# LEDCube.net
KiCad netlist of a schematic drawn in EAGLE
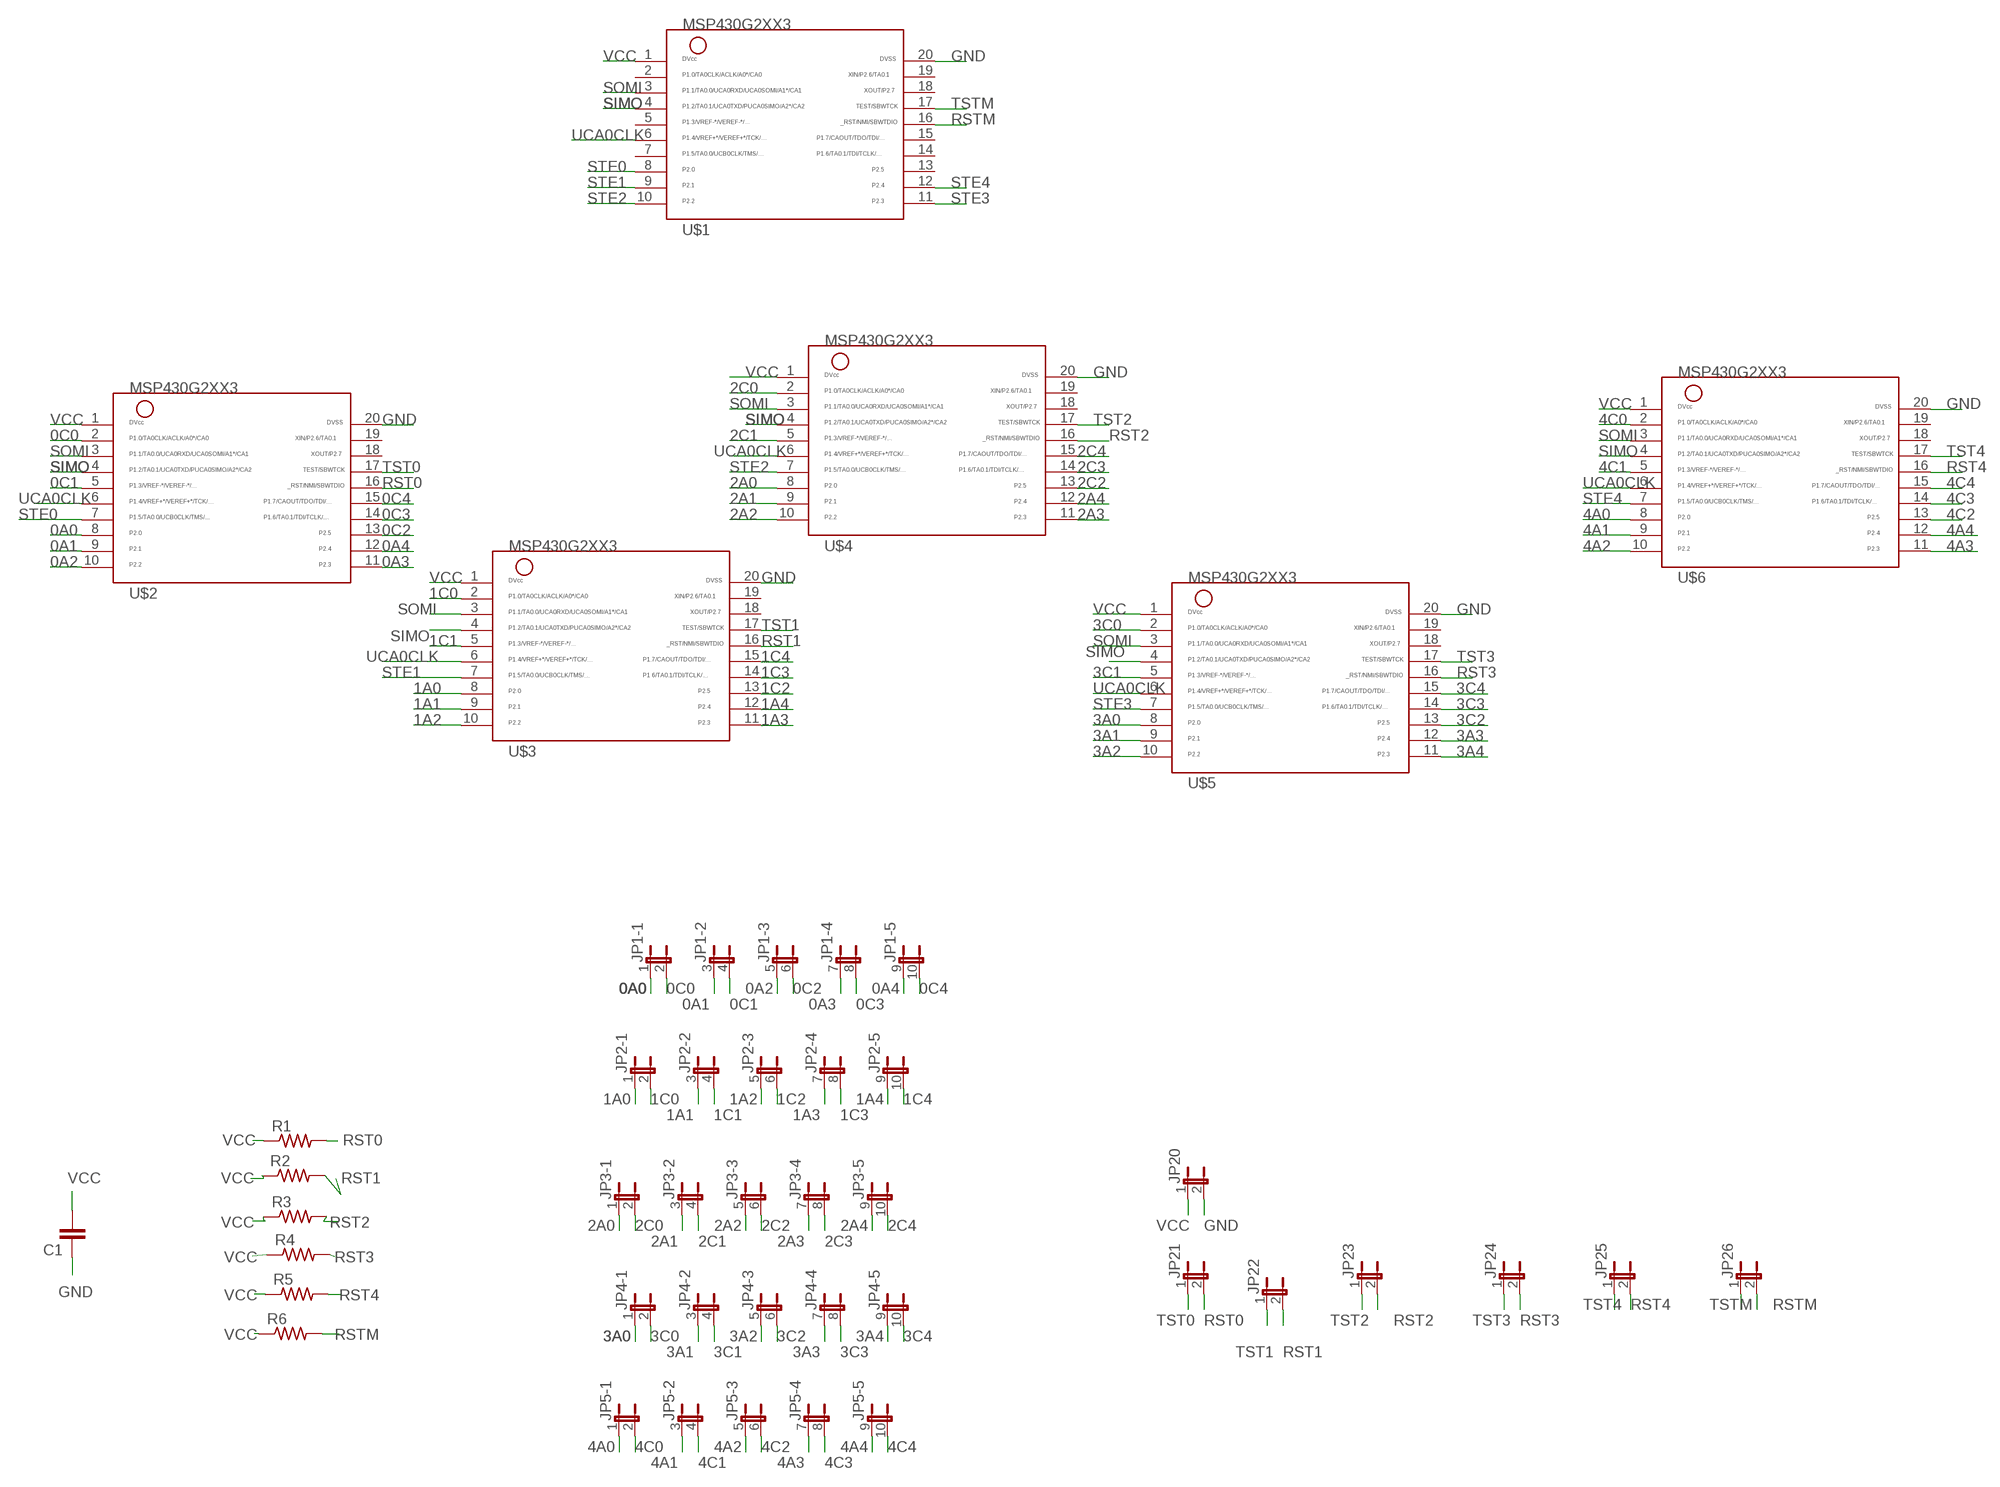
[diagram p0: schematic, sheet 1]

(export (version "E")
  (design (tool "Eeschema 10.0.6"))
  (components
    (comp (ref "C1")
      (value "CC1206")
      (footprint "eagle-import:C1206")
      (libsource (lib "eagle-import") (part "CC1206"))
    )
    (comp (ref "JP1")
      (value "JP5QE")
      (footprint "eagle-import:JP5Q")
      (libsource (lib "eagle-import") (part "JP5QE"))
    )
    (comp (ref "JP2")
      (value "JP5QE")
      (footprint "eagle-import:JP5Q")
      (libsource (lib "eagle-import") (part "JP5QE"))
    )
    (comp (ref "JP3")
      (value "JP5QE")
      (footprint "eagle-import:JP5Q")
      (libsource (lib "eagle-import") (part "JP5QE"))
    )
    (comp (ref "JP4")
      (value "JP5QE")
      (footprint "eagle-import:JP5Q")
      (libsource (lib "eagle-import") (part "JP5QE"))
    )
    (comp (ref "JP5")
      (value "JP5QE")
      (footprint "eagle-import:JP5Q")
      (libsource (lib "eagle-import") (part "JP5QE"))
    )
    (comp (ref "JP20")
      (value "JP1E")
      (footprint "eagle-import:JP1")
      (libsource (lib "eagle-import") (part "JP1E"))
    )
    (comp (ref "JP21")
      (value "JP1E")
      (footprint "eagle-import:JP1")
      (libsource (lib "eagle-import") (part "JP1E"))
    )
    (comp (ref "JP22")
      (value "JP1E")
      (footprint "eagle-import:JP1")
      (libsource (lib "eagle-import") (part "JP1E"))
    )
    (comp (ref "JP23")
      (value "JP1E")
      (footprint "eagle-import:JP1")
      (libsource (lib "eagle-import") (part "JP1E"))
    )
    (comp (ref "JP24")
      (value "JP1E")
      (footprint "eagle-import:JP1")
      (libsource (lib "eagle-import") (part "JP1E"))
    )
    (comp (ref "JP25")
      (value "JP1E")
      (footprint "eagle-import:JP1")
      (libsource (lib "eagle-import") (part "JP1E"))
    )
    (comp (ref "JP26")
      (value "JP1E")
      (footprint "eagle-import:JP1")
      (libsource (lib "eagle-import") (part "JP1E"))
    )
    (comp (ref "R1")
      (value "R-US_R1206")
      (footprint "eagle-import:R1206")
      (libsource (lib "eagle-import") (part "R-US_R1206"))
    )
    (comp (ref "R2")
      (value "R-US_R1206")
      (footprint "eagle-import:R1206")
      (libsource (lib "eagle-import") (part "R-US_R1206"))
    )
    (comp (ref "R3")
      (value "R-US_R1206")
      (footprint "eagle-import:R1206")
      (libsource (lib "eagle-import") (part "R-US_R1206"))
    )
    (comp (ref "R4")
      (value "R-US_R1206")
      (footprint "eagle-import:R1206")
      (libsource (lib "eagle-import") (part "R-US_R1206"))
    )
    (comp (ref "R5")
      (value "R-US_R1206")
      (footprint "eagle-import:R1206")
      (libsource (lib "eagle-import") (part "R-US_R1206"))
    )
    (comp (ref "R6")
      (value "R-US_R1206")
      (footprint "eagle-import:R1206")
      (libsource (lib "eagle-import") (part "R-US_R1206"))
    )
    (comp (ref "U$1")
      (value "MSP430G2XX3TSSOP")
      (footprint "eagle-import:PW20")
      (libsource (lib "eagle-import") (part "MSP430G2XX3TSSOP"))
    )
    (comp (ref "U$2")
      (value "MSP430G2XX3TSSOP")
      (footprint "eagle-import:PW20")
      (libsource (lib "eagle-import") (part "MSP430G2XX3TSSOP"))
    )
    (comp (ref "U$3")
      (value "MSP430G2XX3TSSOP")
      (footprint "eagle-import:PW20")
      (libsource (lib "eagle-import") (part "MSP430G2XX3TSSOP"))
    )
    (comp (ref "U$4")
      (value "MSP430G2XX3TSSOP")
      (footprint "eagle-import:PW20")
      (libsource (lib "eagle-import") (part "MSP430G2XX3TSSOP"))
    )
    (comp (ref "U$5")
      (value "MSP430G2XX3TSSOP")
      (footprint "eagle-import:PW20")
      (libsource (lib "eagle-import") (part "MSP430G2XX3TSSOP"))
    )
    (comp (ref "U$6")
      (value "MSP430G2XX3TSSOP")
      (footprint "eagle-import:PW20")
      (libsource (lib "eagle-import") (part "MSP430G2XX3TSSOP"))
    )
  )
  (nets
    (net (code "1") (name "/0A0") (class "Default")
      (node (ref "JP1") (pin "1") (pinfunction "1_1") (pintype "passive"))
      (node (ref "U$2") (pin "8") (pinfunction "8_8") (pintype "bidirectional"))
    )
    (net (code "2") (name "/0A1") (class "Default")
      (node (ref "JP1") (pin "3") (pinfunction "1_3") (pintype "passive"))
      (node (ref "U$2") (pin "9") (pinfunction "9_9") (pintype "bidirectional"))
    )
    (net (code "3") (name "/0A2") (class "Default")
      (node (ref "JP1") (pin "5") (pinfunction "1_5") (pintype "passive"))
      (node (ref "U$2") (pin "10") (pinfunction "10_10") (pintype "bidirectional"))
    )
    (net (code "4") (name "/0A3") (class "Default")
      (node (ref "JP1") (pin "7") (pinfunction "1_7") (pintype "passive"))
      (node (ref "U$2") (pin "11") (pinfunction "11_11") (pintype "bidirectional"))
    )
    (net (code "5") (name "/0A4") (class "Default")
      (node (ref "JP1") (pin "9") (pinfunction "1_9") (pintype "passive"))
      (node (ref "U$2") (pin "12") (pinfunction "12_12") (pintype "bidirectional"))
    )
    (net (code "6") (name "/0C0") (class "Default")
      (node (ref "JP1") (pin "2") (pinfunction "2_2") (pintype "passive"))
      (node (ref "U$2") (pin "2") (pinfunction "2_2") (pintype "bidirectional"))
    )
    (net (code "7") (name "/0C1") (class "Default")
      (node (ref "JP1") (pin "4") (pinfunction "2_4") (pintype "passive"))
      (node (ref "U$2") (pin "5") (pinfunction "5_5") (pintype "bidirectional"))
    )
    (net (code "8") (name "/0C2") (class "Default")
      (node (ref "JP1") (pin "6") (pinfunction "2_6") (pintype "passive"))
      (node (ref "U$2") (pin "13") (pinfunction "13_13") (pintype "bidirectional"))
    )
    (net (code "9") (name "/0C3") (class "Default")
      (node (ref "JP1") (pin "8") (pinfunction "2_8") (pintype "passive"))
      (node (ref "U$2") (pin "14") (pinfunction "14_14") (pintype "bidirectional"))
    )
    (net (code "10") (name "/0C4") (class "Default")
      (node (ref "JP1") (pin "10") (pinfunction "2_10") (pintype "passive"))
      (node (ref "U$2") (pin "15") (pinfunction "15_15") (pintype "bidirectional"))
    )
    (net (code "11") (name "/1A0") (class "Default")
      (node (ref "JP2") (pin "1") (pinfunction "1_1") (pintype "passive"))
      (node (ref "U$3") (pin "8") (pinfunction "8_8") (pintype "bidirectional"))
    )
    (net (code "12") (name "/1A1") (class "Default")
      (node (ref "JP2") (pin "3") (pinfunction "1_3") (pintype "passive"))
      (node (ref "U$3") (pin "9") (pinfunction "9_9") (pintype "bidirectional"))
    )
    (net (code "13") (name "/1A2") (class "Default")
      (node (ref "JP2") (pin "5") (pinfunction "1_5") (pintype "passive"))
      (node (ref "U$3") (pin "10") (pinfunction "10_10") (pintype "bidirectional"))
    )
    (net (code "14") (name "/1A3") (class "Default")
      (node (ref "JP2") (pin "7") (pinfunction "1_7") (pintype "passive"))
      (node (ref "U$3") (pin "11") (pinfunction "11_11") (pintype "bidirectional"))
    )
    (net (code "15") (name "/1A4") (class "Default")
      (node (ref "JP2") (pin "9") (pinfunction "1_9") (pintype "passive"))
      (node (ref "U$3") (pin "12") (pinfunction "12_12") (pintype "bidirectional"))
    )
    (net (code "16") (name "/1C0") (class "Default")
      (node (ref "JP2") (pin "2") (pinfunction "2_2") (pintype "passive"))
      (node (ref "U$3") (pin "2") (pinfunction "2_2") (pintype "bidirectional"))
    )
    (net (code "17") (name "/1C1") (class "Default")
      (node (ref "JP2") (pin "4") (pinfunction "2_4") (pintype "passive"))
      (node (ref "U$3") (pin "5") (pinfunction "5_5") (pintype "bidirectional"))
    )
    (net (code "18") (name "/1C2") (class "Default")
      (node (ref "JP2") (pin "6") (pinfunction "2_6") (pintype "passive"))
      (node (ref "U$3") (pin "13") (pinfunction "13_13") (pintype "bidirectional"))
    )
    (net (code "19") (name "/1C3") (class "Default")
      (node (ref "JP2") (pin "8") (pinfunction "2_8") (pintype "passive"))
      (node (ref "U$3") (pin "14") (pinfunction "14_14") (pintype "bidirectional"))
    )
    (net (code "20") (name "/1C4") (class "Default")
      (node (ref "JP2") (pin "10") (pinfunction "2_10") (pintype "passive"))
      (node (ref "U$3") (pin "15") (pinfunction "15_15") (pintype "bidirectional"))
    )
    (net (code "21") (name "/2A0") (class "Default")
      (node (ref "JP3") (pin "1") (pinfunction "1_1") (pintype "passive"))
      (node (ref "U$4") (pin "8") (pinfunction "8_8") (pintype "bidirectional"))
    )
    (net (code "22") (name "/2A1") (class "Default")
      (node (ref "JP3") (pin "3") (pinfunction "1_3") (pintype "passive"))
      (node (ref "U$4") (pin "9") (pinfunction "9_9") (pintype "bidirectional"))
    )
    (net (code "23") (name "/2A2") (class "Default")
      (node (ref "JP3") (pin "5") (pinfunction "1_5") (pintype "passive"))
      (node (ref "U$4") (pin "10") (pinfunction "10_10") (pintype "bidirectional"))
    )
    (net (code "24") (name "/2A3") (class "Default")
      (node (ref "JP3") (pin "7") (pinfunction "1_7") (pintype "passive"))
      (node (ref "U$4") (pin "11") (pinfunction "11_11") (pintype "bidirectional"))
    )
    (net (code "25") (name "/2A4") (class "Default")
      (node (ref "JP3") (pin "9") (pinfunction "1_9") (pintype "passive"))
      (node (ref "U$4") (pin "12") (pinfunction "12_12") (pintype "bidirectional"))
    )
    (net (code "26") (name "/2C0") (class "Default")
      (node (ref "JP3") (pin "2") (pinfunction "2_2") (pintype "passive"))
      (node (ref "U$4") (pin "2") (pinfunction "2_2") (pintype "bidirectional"))
    )
    (net (code "27") (name "/2C1") (class "Default")
      (node (ref "JP3") (pin "4") (pinfunction "2_4") (pintype "passive"))
      (node (ref "U$4") (pin "5") (pinfunction "5_5") (pintype "bidirectional"))
    )
    (net (code "28") (name "/2C2") (class "Default")
      (node (ref "JP3") (pin "6") (pinfunction "2_6") (pintype "passive"))
      (node (ref "U$4") (pin "13") (pinfunction "13_13") (pintype "bidirectional"))
    )
    (net (code "29") (name "/2C3") (class "Default")
      (node (ref "JP3") (pin "8") (pinfunction "2_8") (pintype "passive"))
      (node (ref "U$4") (pin "14") (pinfunction "14_14") (pintype "bidirectional"))
    )
    (net (code "30") (name "/2C4") (class "Default")
      (node (ref "JP3") (pin "10") (pinfunction "2_10") (pintype "passive"))
      (node (ref "U$4") (pin "15") (pinfunction "15_15") (pintype "bidirectional"))
    )
    (net (code "31") (name "/3A0") (class "Default")
      (node (ref "JP4") (pin "1") (pinfunction "1_1") (pintype "passive"))
      (node (ref "U$5") (pin "8") (pinfunction "8_8") (pintype "bidirectional"))
    )
    (net (code "32") (name "/3A1") (class "Default")
      (node (ref "JP4") (pin "3") (pinfunction "1_3") (pintype "passive"))
      (node (ref "U$5") (pin "9") (pinfunction "9_9") (pintype "bidirectional"))
    )
    (net (code "33") (name "/3A2") (class "Default")
      (node (ref "JP4") (pin "5") (pinfunction "1_5") (pintype "passive"))
      (node (ref "U$5") (pin "10") (pinfunction "10_10") (pintype "bidirectional"))
    )
    (net (code "34") (name "/3A3") (class "Default")
      (node (ref "JP4") (pin "7") (pinfunction "1_7") (pintype "passive"))
      (node (ref "U$5") (pin "12") (pinfunction "12_12") (pintype "bidirectional"))
    )
    (net (code "35") (name "/3A4") (class "Default")
      (node (ref "JP4") (pin "9") (pinfunction "1_9") (pintype "passive"))
      (node (ref "U$5") (pin "11") (pinfunction "11_11") (pintype "bidirectional"))
    )
    (net (code "36") (name "/3C0") (class "Default")
      (node (ref "JP4") (pin "2") (pinfunction "2_2") (pintype "passive"))
      (node (ref "U$5") (pin "2") (pinfunction "2_2") (pintype "bidirectional"))
    )
    (net (code "37") (name "/3C1") (class "Default")
      (node (ref "JP4") (pin "4") (pinfunction "2_4") (pintype "passive"))
      (node (ref "U$5") (pin "5") (pinfunction "5_5") (pintype "bidirectional"))
    )
    (net (code "38") (name "/3C2") (class "Default")
      (node (ref "JP4") (pin "6") (pinfunction "2_6") (pintype "passive"))
      (node (ref "U$5") (pin "13") (pinfunction "13_13") (pintype "bidirectional"))
    )
    (net (code "39") (name "/3C3") (class "Default")
      (node (ref "JP4") (pin "8") (pinfunction "2_8") (pintype "passive"))
      (node (ref "U$5") (pin "14") (pinfunction "14_14") (pintype "bidirectional"))
    )
    (net (code "40") (name "/3C4") (class "Default")
      (node (ref "JP4") (pin "10") (pinfunction "2_10") (pintype "passive"))
      (node (ref "U$5") (pin "15") (pinfunction "15_15") (pintype "bidirectional"))
    )
    (net (code "41") (name "/4A0") (class "Default")
      (node (ref "JP5") (pin "1") (pinfunction "1_1") (pintype "passive"))
      (node (ref "U$6") (pin "8") (pinfunction "8_8") (pintype "bidirectional"))
    )
    (net (code "42") (name "/4A1") (class "Default")
      (node (ref "JP5") (pin "3") (pinfunction "1_3") (pintype "passive"))
      (node (ref "U$6") (pin "9") (pinfunction "9_9") (pintype "bidirectional"))
    )
    (net (code "43") (name "/4A2") (class "Default")
      (node (ref "JP5") (pin "5") (pinfunction "1_5") (pintype "passive"))
      (node (ref "U$6") (pin "10") (pinfunction "10_10") (pintype "bidirectional"))
    )
    (net (code "44") (name "/4A3") (class "Default")
      (node (ref "JP5") (pin "7") (pinfunction "1_7") (pintype "passive"))
      (node (ref "U$6") (pin "11") (pinfunction "11_11") (pintype "bidirectional"))
    )
    (net (code "45") (name "/4A4") (class "Default")
      (node (ref "JP5") (pin "9") (pinfunction "1_9") (pintype "passive"))
      (node (ref "U$6") (pin "12") (pinfunction "12_12") (pintype "bidirectional"))
    )
    (net (code "46") (name "/4C0") (class "Default")
      (node (ref "JP5") (pin "2") (pinfunction "2_2") (pintype "passive"))
      (node (ref "U$6") (pin "2") (pinfunction "2_2") (pintype "bidirectional"))
    )
    (net (code "47") (name "/4C1") (class "Default")
      (node (ref "JP5") (pin "4") (pinfunction "2_4") (pintype "passive"))
      (node (ref "U$6") (pin "5") (pinfunction "5_5") (pintype "bidirectional"))
    )
    (net (code "48") (name "/4C2") (class "Default")
      (node (ref "JP5") (pin "6") (pinfunction "2_6") (pintype "passive"))
      (node (ref "U$6") (pin "13") (pinfunction "13_13") (pintype "bidirectional"))
    )
    (net (code "49") (name "/4C3") (class "Default")
      (node (ref "JP5") (pin "8") (pinfunction "2_8") (pintype "passive"))
      (node (ref "U$6") (pin "14") (pinfunction "14_14") (pintype "bidirectional"))
    )
    (net (code "50") (name "/4C4") (class "Default")
      (node (ref "JP5") (pin "10") (pinfunction "2_10") (pintype "passive"))
      (node (ref "U$6") (pin "15") (pinfunction "15_15") (pintype "bidirectional"))
    )
    (net (code "51") (name "/GND") (class "Default")
      (node (ref "C1") (pin "1") (pinfunction "1_1") (pintype "passive"))
      (node (ref "JP20") (pin "2") (pinfunction "2_2") (pintype "passive"))
      (node (ref "U$1") (pin "20") (pinfunction "20_20") (pintype "bidirectional"))
      (node (ref "U$2") (pin "20") (pinfunction "20_20") (pintype "bidirectional"))
      (node (ref "U$3") (pin "20") (pinfunction "20_20") (pintype "bidirectional"))
      (node (ref "U$4") (pin "20") (pinfunction "20_20") (pintype "bidirectional"))
      (node (ref "U$5") (pin "20") (pinfunction "20_20") (pintype "bidirectional"))
      (node (ref "U$6") (pin "20") (pinfunction "20_20") (pintype "bidirectional"))
    )
    (net (code "52") (name "/RST0") (class "Default")
      (node (ref "JP21") (pin "2") (pinfunction "2_2") (pintype "passive"))
      (node (ref "R1") (pin "2") (pinfunction "2_2") (pintype "passive"))
      (node (ref "U$2") (pin "16") (pinfunction "16_16") (pintype "bidirectional"))
    )
    (net (code "53") (name "/RST1") (class "Default")
      (node (ref "JP22") (pin "2") (pinfunction "2_2") (pintype "passive"))
      (node (ref "R2") (pin "2") (pinfunction "2_2") (pintype "passive"))
      (node (ref "U$3") (pin "16") (pinfunction "16_16") (pintype "bidirectional"))
    )
    (net (code "54") (name "/RST2") (class "Default")
      (node (ref "JP23") (pin "2") (pinfunction "2_2") (pintype "passive"))
      (node (ref "R3") (pin "2") (pinfunction "2_2") (pintype "passive"))
      (node (ref "U$4") (pin "16") (pinfunction "16_16") (pintype "bidirectional"))
    )
    (net (code "55") (name "/RST3") (class "Default")
      (node (ref "JP24") (pin "2") (pinfunction "2_2") (pintype "passive"))
      (node (ref "R4") (pin "2") (pinfunction "2_2") (pintype "passive"))
      (node (ref "U$5") (pin "16") (pinfunction "16_16") (pintype "bidirectional"))
    )
    (net (code "56") (name "/RST4") (class "Default")
      (node (ref "JP25") (pin "2") (pinfunction "2_2") (pintype "passive"))
      (node (ref "R5") (pin "2") (pinfunction "2_2") (pintype "passive"))
      (node (ref "U$6") (pin "16") (pinfunction "16_16") (pintype "bidirectional"))
    )
    (net (code "57") (name "/RSTM") (class "Default")
      (node (ref "JP26") (pin "2") (pinfunction "2_2") (pintype "passive"))
      (node (ref "R6") (pin "2") (pinfunction "2_2") (pintype "passive"))
      (node (ref "U$1") (pin "16") (pinfunction "16_16") (pintype "bidirectional"))
    )
    (net (code "58") (name "/SIMO") (class "Default")
      (node (ref "U$1") (pin "4") (pinfunction "4_4") (pintype "bidirectional"))
      (node (ref "U$2") (pin "4") (pinfunction "4_4") (pintype "bidirectional"))
      (node (ref "U$3") (pin "4") (pinfunction "4_4") (pintype "bidirectional"))
      (node (ref "U$4") (pin "4") (pinfunction "4_4") (pintype "bidirectional"))
      (node (ref "U$5") (pin "4") (pinfunction "4_4") (pintype "bidirectional"))
      (node (ref "U$6") (pin "4") (pinfunction "4_4") (pintype "bidirectional"))
    )
    (net (code "59") (name "/SOMI") (class "Default")
      (node (ref "U$1") (pin "3") (pinfunction "3_3") (pintype "bidirectional"))
      (node (ref "U$2") (pin "3") (pinfunction "3_3") (pintype "bidirectional"))
      (node (ref "U$3") (pin "3") (pinfunction "3_3") (pintype "bidirectional"))
      (node (ref "U$4") (pin "3") (pinfunction "3_3") (pintype "bidirectional"))
      (node (ref "U$5") (pin "3") (pinfunction "3_3") (pintype "bidirectional"))
      (node (ref "U$6") (pin "3") (pinfunction "3_3") (pintype "bidirectional"))
    )
    (net (code "60") (name "/STE0") (class "Default")
      (node (ref "U$1") (pin "8") (pinfunction "8_8") (pintype "bidirectional"))
      (node (ref "U$2") (pin "7") (pinfunction "7_7") (pintype "bidirectional"))
    )
    (net (code "61") (name "/STE1") (class "Default")
      (node (ref "U$1") (pin "9") (pinfunction "9_9") (pintype "bidirectional"))
      (node (ref "U$3") (pin "7") (pinfunction "7_7") (pintype "bidirectional"))
    )
    (net (code "62") (name "/STE2") (class "Default")
      (node (ref "U$1") (pin "10") (pinfunction "10_10") (pintype "bidirectional"))
      (node (ref "U$4") (pin "7") (pinfunction "7_7") (pintype "bidirectional"))
    )
    (net (code "63") (name "/STE3") (class "Default")
      (node (ref "U$1") (pin "11") (pinfunction "11_11") (pintype "bidirectional"))
      (node (ref "U$5") (pin "7") (pinfunction "7_7") (pintype "bidirectional"))
    )
    (net (code "64") (name "/STE4") (class "Default")
      (node (ref "U$1") (pin "12") (pinfunction "12_12") (pintype "bidirectional"))
      (node (ref "U$6") (pin "7") (pinfunction "7_7") (pintype "bidirectional"))
    )
    (net (code "65") (name "/TST0") (class "Default")
      (node (ref "JP21") (pin "1") (pinfunction "1_1") (pintype "passive"))
      (node (ref "U$2") (pin "17") (pinfunction "17_17") (pintype "bidirectional"))
    )
    (net (code "66") (name "/TST1") (class "Default")
      (node (ref "JP22") (pin "1") (pinfunction "1_1") (pintype "passive"))
      (node (ref "U$3") (pin "17") (pinfunction "17_17") (pintype "bidirectional"))
    )
    (net (code "67") (name "/TST2") (class "Default")
      (node (ref "JP23") (pin "1") (pinfunction "1_1") (pintype "passive"))
      (node (ref "U$4") (pin "17") (pinfunction "17_17") (pintype "bidirectional"))
    )
    (net (code "68") (name "/TST3") (class "Default")
      (node (ref "JP24") (pin "1") (pinfunction "1_1") (pintype "passive"))
      (node (ref "U$5") (pin "17") (pinfunction "17_17") (pintype "bidirectional"))
    )
    (net (code "69") (name "/TST4") (class "Default")
      (node (ref "JP25") (pin "1") (pinfunction "1_1") (pintype "passive"))
      (node (ref "U$6") (pin "17") (pinfunction "17_17") (pintype "bidirectional"))
    )
    (net (code "70") (name "/TSTM") (class "Default")
      (node (ref "JP26") (pin "1") (pinfunction "1_1") (pintype "passive"))
      (node (ref "U$1") (pin "17") (pinfunction "17_17") (pintype "bidirectional"))
    )
    (net (code "71") (name "/UCA0CLK") (class "Default")
      (node (ref "U$1") (pin "6") (pinfunction "6_6") (pintype "bidirectional"))
      (node (ref "U$2") (pin "6") (pinfunction "6_6") (pintype "bidirectional"))
      (node (ref "U$3") (pin "6") (pinfunction "6_6") (pintype "bidirectional"))
      (node (ref "U$4") (pin "6") (pinfunction "6_6") (pintype "bidirectional"))
      (node (ref "U$5") (pin "6") (pinfunction "6_6") (pintype "bidirectional"))
      (node (ref "U$6") (pin "6") (pinfunction "6_6") (pintype "bidirectional"))
    )
    (net (code "72") (name "/VCC") (class "Default")
      (node (ref "C1") (pin "2") (pinfunction "2_2") (pintype "passive"))
      (node (ref "JP20") (pin "1") (pinfunction "1_1") (pintype "passive"))
      (node (ref "R1") (pin "1") (pinfunction "1_1") (pintype "passive"))
      (node (ref "R2") (pin "1") (pinfunction "1_1") (pintype "passive"))
      (node (ref "R3") (pin "1") (pinfunction "1_1") (pintype "passive"))
      (node (ref "R4") (pin "1") (pinfunction "1_1") (pintype "passive"))
      (node (ref "R5") (pin "1") (pinfunction "1_1") (pintype "passive"))
      (node (ref "R6") (pin "1") (pinfunction "1_1") (pintype "passive"))
      (node (ref "U$1") (pin "1") (pinfunction "1_1") (pintype "bidirectional"))
      (node (ref "U$2") (pin "1") (pinfunction "1_1") (pintype "bidirectional"))
      (node (ref "U$3") (pin "1") (pinfunction "1_1") (pintype "bidirectional"))
      (node (ref "U$4") (pin "1") (pinfunction "1_1") (pintype "bidirectional"))
      (node (ref "U$5") (pin "1") (pinfunction "1_1") (pintype "bidirectional"))
      (node (ref "U$6") (pin "1") (pinfunction "1_1") (pintype "bidirectional"))
    )
    (net (code "73") (name "unconnected-(U$1-Pad2)") (class "Default")
      (node (ref "U$1") (pin "2") (pinfunction "2_2") (pintype "bidirectional"))
    )
    (net (code "74") (name "unconnected-(U$1-Pad5)") (class "Default")
      (node (ref "U$1") (pin "5") (pinfunction "5_5") (pintype "bidirectional"))
    )
    (net (code "75") (name "unconnected-(U$1-Pad7)") (class "Default")
      (node (ref "U$1") (pin "7") (pinfunction "7_7") (pintype "bidirectional"))
    )
    (net (code "76") (name "unconnected-(U$1-Pad13)") (class "Default")
      (node (ref "U$1") (pin "13") (pinfunction "13_13") (pintype "bidirectional"))
    )
    (net (code "77") (name "unconnected-(U$1-Pad14)") (class "Default")
      (node (ref "U$1") (pin "14") (pinfunction "14_14") (pintype "bidirectional"))
    )
    (net (code "78") (name "unconnected-(U$1-Pad15)") (class "Default")
      (node (ref "U$1") (pin "15") (pinfunction "15_15") (pintype "bidirectional"))
    )
    (net (code "79") (name "unconnected-(U$1-Pad18)") (class "Default")
      (node (ref "U$1") (pin "18") (pinfunction "18_18") (pintype "bidirectional"))
    )
    (net (code "80") (name "unconnected-(U$1-Pad19)") (class "Default")
      (node (ref "U$1") (pin "19") (pinfunction "19_19") (pintype "bidirectional"))
    )
    (net (code "81") (name "unconnected-(U$2-Pad18)") (class "Default")
      (node (ref "U$2") (pin "18") (pinfunction "18_18") (pintype "bidirectional"))
    )
    (net (code "82") (name "unconnected-(U$2-Pad19)") (class "Default")
      (node (ref "U$2") (pin "19") (pinfunction "19_19") (pintype "bidirectional"))
    )
    (net (code "83") (name "unconnected-(U$3-Pad18)") (class "Default")
      (node (ref "U$3") (pin "18") (pinfunction "18_18") (pintype "bidirectional"))
    )
    (net (code "84") (name "unconnected-(U$3-Pad19)") (class "Default")
      (node (ref "U$3") (pin "19") (pinfunction "19_19") (pintype "bidirectional"))
    )
    (net (code "85") (name "unconnected-(U$4-Pad18)") (class "Default")
      (node (ref "U$4") (pin "18") (pinfunction "18_18") (pintype "bidirectional"))
    )
    (net (code "86") (name "unconnected-(U$4-Pad19)") (class "Default")
      (node (ref "U$4") (pin "19") (pinfunction "19_19") (pintype "bidirectional"))
    )
    (net (code "87") (name "unconnected-(U$5-Pad18)") (class "Default")
      (node (ref "U$5") (pin "18") (pinfunction "18_18") (pintype "bidirectional"))
    )
    (net (code "88") (name "unconnected-(U$5-Pad19)") (class "Default")
      (node (ref "U$5") (pin "19") (pinfunction "19_19") (pintype "bidirectional"))
    )
    (net (code "89") (name "unconnected-(U$6-Pad18)") (class "Default")
      (node (ref "U$6") (pin "18") (pinfunction "18_18") (pintype "bidirectional"))
    )
    (net (code "90") (name "unconnected-(U$6-Pad19)") (class "Default")
      (node (ref "U$6") (pin "19") (pinfunction "19_19") (pintype "bidirectional"))
    )
  )
)
